# ArduinoBoardPOE.net
KiCad netlist of a schematic drawn in EAGLE
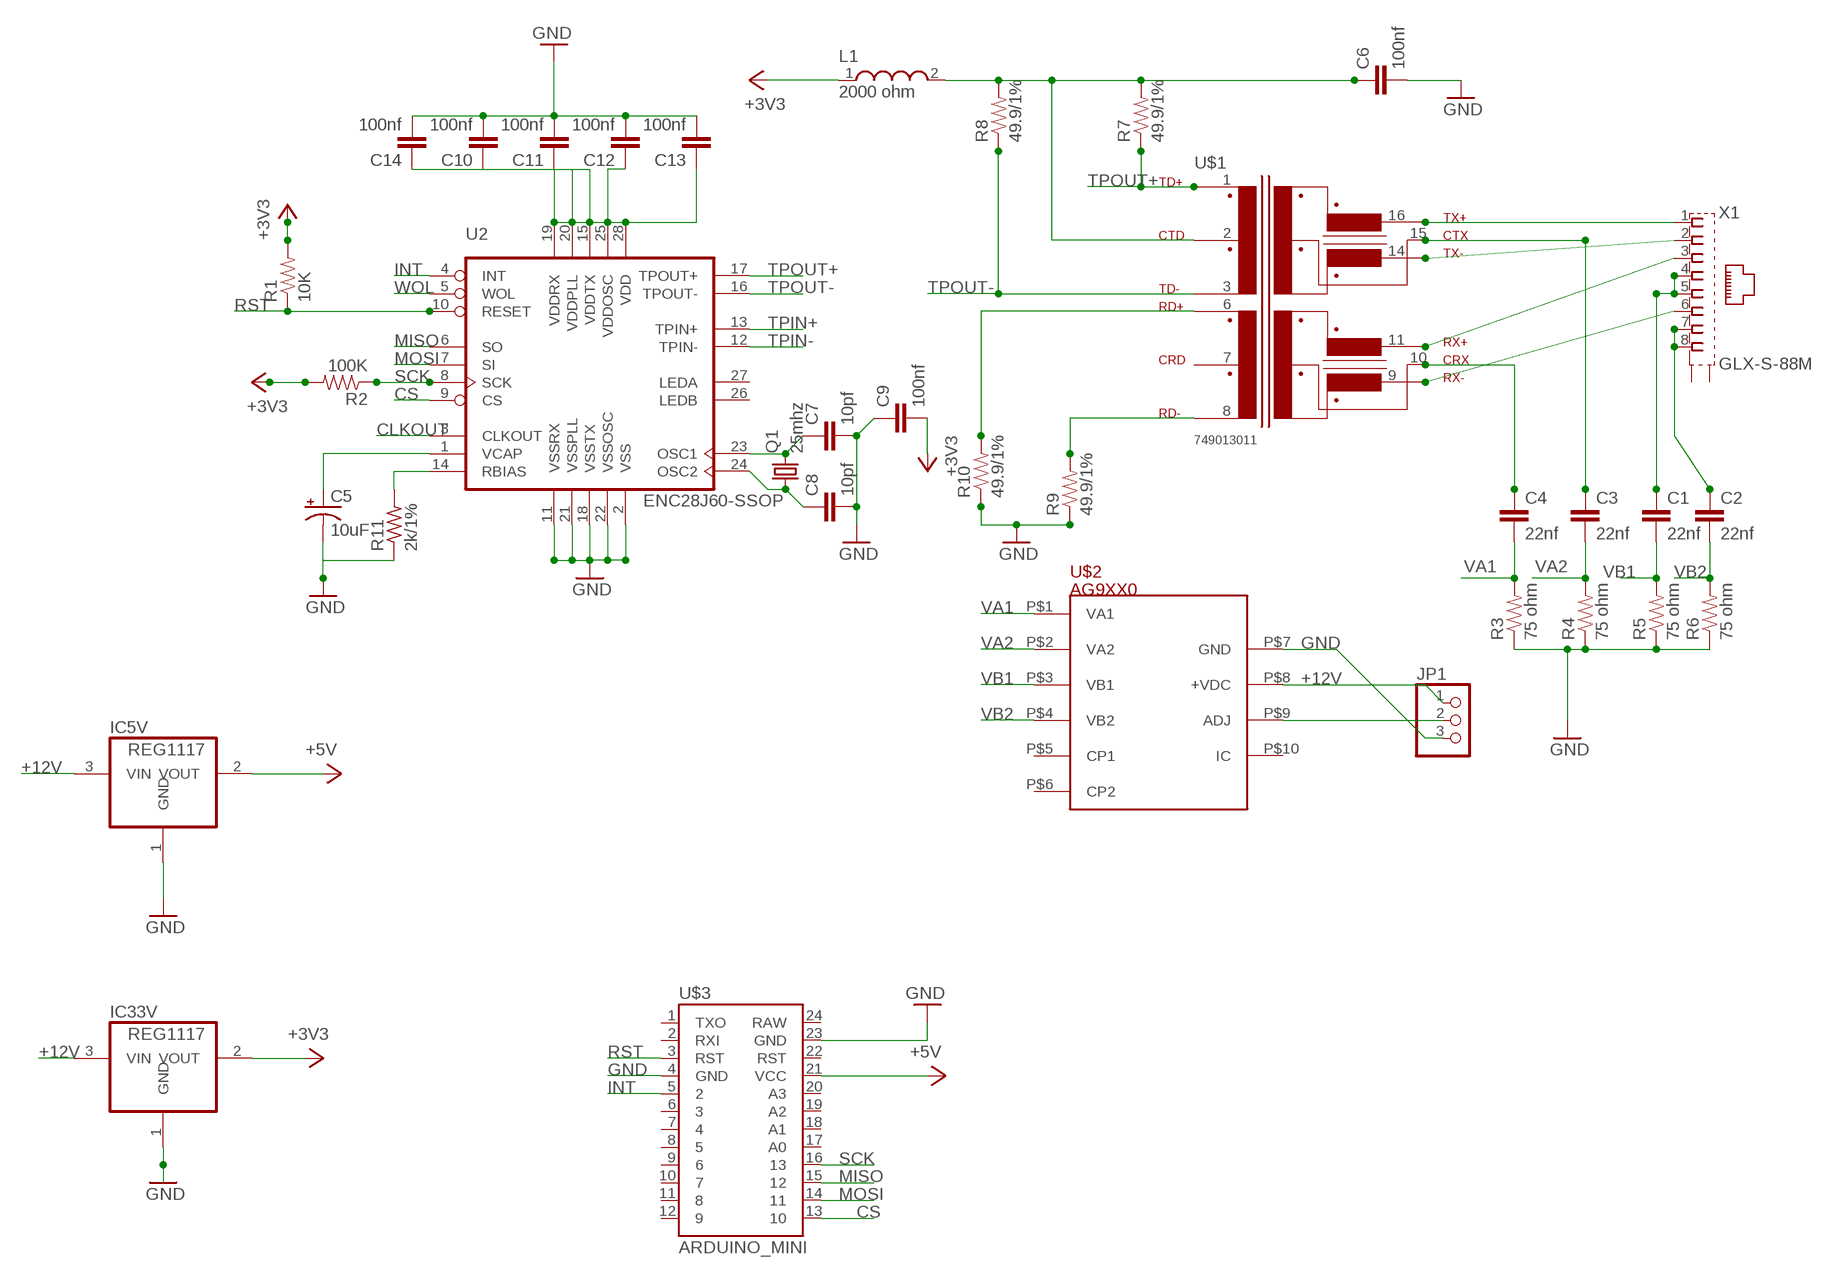
[diagram p0: schematic, sheet 1]

(export (version "E")
  (design (tool "Eeschema 10.0.6"))
  (components
    (comp (ref "C1")
      (value "22nf")
      (footprint "eagle-import:0805")
      (libsource (lib "eagle-import") (part "CAP0805"))
    )
    (comp (ref "C2")
      (value "22nf")
      (footprint "eagle-import:0805")
      (libsource (lib "eagle-import") (part "CAP0805"))
    )
    (comp (ref "C3")
      (value "22nf")
      (footprint "eagle-import:0805")
      (libsource (lib "eagle-import") (part "CAP0805"))
    )
    (comp (ref "C4")
      (value "22nf")
      (footprint "eagle-import:0805")
      (libsource (lib "eagle-import") (part "CAP0805"))
    )
    (comp (ref "C5")
      (value "10uF")
      (footprint "eagle-import:EIA3216")
      (libsource (lib "eagle-import") (part "10UF-16V-10%(TANT)"))
    )
    (comp (ref "C6")
      (value "100nf")
      (footprint "eagle-import:0805")
      (libsource (lib "eagle-import") (part "CAP0805"))
    )
    (comp (ref "C7")
      (value "10pf")
      (footprint "eagle-import:0805")
      (libsource (lib "eagle-import") (part "CAP0805"))
    )
    (comp (ref "C8")
      (value "10pf")
      (footprint "eagle-import:0805")
      (libsource (lib "eagle-import") (part "CAP0805"))
    )
    (comp (ref "C9")
      (value "100nf")
      (footprint "eagle-import:0805")
      (libsource (lib "eagle-import") (part "CAP0805"))
    )
    (comp (ref "C10")
      (value "100nf")
      (footprint "eagle-import:0805")
      (libsource (lib "eagle-import") (part "CAP0805"))
    )
    (comp (ref "C11")
      (value "100nf")
      (footprint "eagle-import:0805")
      (libsource (lib "eagle-import") (part "CAP0805"))
    )
    (comp (ref "C12")
      (value "100nf")
      (footprint "eagle-import:0805")
      (libsource (lib "eagle-import") (part "CAP0805"))
    )
    (comp (ref "C13")
      (value "100nf")
      (footprint "eagle-import:0805")
      (libsource (lib "eagle-import") (part "CAP0805"))
    )
    (comp (ref "C14")
      (value "100nf")
      (footprint "eagle-import:0805")
      (libsource (lib "eagle-import") (part "CAP0805"))
    )
    (comp (ref "IC5V")
      (value "REG1117")
      (footprint "eagle-import:SOT223")
      (libsource (lib "eagle-import") (part "REG1117"))
    )
    (comp (ref "IC33V")
      (value "REG1117")
      (footprint "eagle-import:SOT223")
      (libsource (lib "eagle-import") (part "REG1117"))
    )
    (comp (ref "JP1")
      (value "PINHD-1X3")
      (footprint "eagle-import:1X03")
      (libsource (lib "eagle-import") (part "PINHD-1X3"))
    )
    (comp (ref "L1")
      (value "2000 ohm")
      (footprint "eagle-import:WE-CBA_0805(W=3)")
      (libsource (lib "eagle-import") (part "WE-CBA_0805(WB/HS)"))
    )
    (comp (ref "Q1")
      (value "25mhz")
      (footprint "eagle-import:HC49UP")
      (libsource (lib "eagle-import") (part "CRYSTALHC49UP"))
    )
    (comp (ref "R1")
      (value "10K")
      (footprint "eagle-import:0805")
      (libsource (lib "eagle-import") (part "RESISTOR0805-RES"))
    )
    (comp (ref "R2")
      (value "100K")
      (footprint "eagle-import:0805")
      (libsource (lib "eagle-import") (part "RESISTOR0805-RES"))
    )
    (comp (ref "R3")
      (value "75 ohm")
      (footprint "eagle-import:0805")
      (libsource (lib "eagle-import") (part "RESISTOR0805-RES"))
    )
    (comp (ref "R4")
      (value "75 ohm")
      (footprint "eagle-import:0805")
      (libsource (lib "eagle-import") (part "RESISTOR0805-RES"))
    )
    (comp (ref "R5")
      (value "75 ohm")
      (footprint "eagle-import:0805")
      (libsource (lib "eagle-import") (part "RESISTOR0805-RES"))
    )
    (comp (ref "R6")
      (value "75 ohm")
      (footprint "eagle-import:0805")
      (libsource (lib "eagle-import") (part "RESISTOR0805-RES"))
    )
    (comp (ref "R7")
      (value "49.9/1%")
      (footprint "eagle-import:0805")
      (libsource (lib "eagle-import") (part "RESISTOR0805-RES"))
    )
    (comp (ref "R8")
      (value "49.9/1%")
      (footprint "eagle-import:0805")
      (libsource (lib "eagle-import") (part "RESISTOR0805-RES"))
    )
    (comp (ref "R9")
      (value "49.9/1%")
      (footprint "eagle-import:0805")
      (libsource (lib "eagle-import") (part "RESISTOR0805-RES"))
    )
    (comp (ref "R10")
      (value "49.9/1%")
      (footprint "eagle-import:0805")
      (libsource (lib "eagle-import") (part "RESISTOR0805-RES"))
    )
    (comp (ref "R11")
      (value "2k/1%")
      (footprint "eagle-import:R0805")
      (libsource (lib "eagle-import") (part "R-US_R0805"))
    )
    (comp (ref "U$1")
      (value "749013011")
      (footprint "eagle-import:749013011")
      (libsource (lib "eagle-import") (part "749013011"))
    )
    (comp (ref "U$2")
      (value "AG9XX0")
      (footprint "eagle-import:AG9000")
      (libsource (lib "eagle-import") (part "AG9XX0"))
    )
    (comp (ref "U$3")
      (value "ARDUINO_MINI")
      (footprint "eagle-import:ARDUINO_MINI")
      (libsource (lib "eagle-import") (part "ARDUINO_MINI"))
    )
    (comp (ref "U2")
      (value "ENC28J60-SSOP")
      (footprint "eagle-import:SSOP28")
      (libsource (lib "eagle-import") (part "ENC28J60-SSOP"))
    )
    (comp (ref "X1")
      (value "GLX-S-88M")
      (footprint "eagle-import:GLX-S-88M")
      (libsource (lib "eagle-import") (part "GLX-S-88M"))
    )
  )
  (nets
    (net (code "1") (name "+3V3") (class "Default")
      (node (ref "C9") (pin "2") (pinfunction "2_2") (pintype "passive"))
      (node (ref "IC33V") (pin "2") (pinfunction "VOUT_2") (pintype "output"))
      (node (ref "L1") (pin "1") (pinfunction "1_1") (pintype "passive"))
      (node (ref "R1") (pin "2") (pinfunction "2_2") (pintype "passive"))
      (node (ref "R2") (pin "2") (pinfunction "2_2") (pintype "passive"))
    )
    (net (code "2") (name "+5V") (class "Default")
      (node (ref "IC5V") (pin "2") (pinfunction "VOUT_2") (pintype "output"))
      (node (ref "U$3") (pin "21") (pinfunction "VCC_21") (pintype "bidirectional"))
    )
    (net (code "3") (name "/+12V") (class "Default")
      (node (ref "IC33V") (pin "3") (pinfunction "VIN_3") (pintype "input"))
      (node (ref "IC5V") (pin "3") (pinfunction "VIN_3") (pintype "input"))
      (node (ref "JP1") (pin "1") (pinfunction "1_1") (pintype "passive"))
      (node (ref "U$2") (pin "P$8") (pinfunction "+VDC_P$8") (pintype "power_in"))
    )
    (net (code "4") (name "/CLKOUT") (class "Default")
      (node (ref "U2") (pin "3") (pinfunction "CLKOUT_3") (pintype "output"))
    )
    (net (code "5") (name "/CS") (class "Default")
      (node (ref "U$3") (pin "13") (pinfunction "10_13") (pintype "bidirectional"))
      (node (ref "U2") (pin "9") (pinfunction "CS_9") (pintype "input"))
    )
    (net (code "6") (name "/INT") (class "Default")
      (node (ref "U$3") (pin "5") (pinfunction "2_5") (pintype "bidirectional"))
      (node (ref "U2") (pin "4") (pinfunction "INT_4") (pintype "output"))
    )
    (net (code "7") (name "/MISO") (class "Default")
      (node (ref "U$3") (pin "15") (pinfunction "12_15") (pintype "bidirectional"))
      (node (ref "U2") (pin "6") (pinfunction "SO_6") (pintype "output"))
    )
    (net (code "8") (name "/MOSI") (class "Default")
      (node (ref "U$3") (pin "14") (pinfunction "11_14") (pintype "bidirectional"))
      (node (ref "U2") (pin "7") (pinfunction "SI_7") (pintype "input"))
    )
    (net (code "9") (name "/RST") (class "Default")
      (node (ref "R1") (pin "1") (pinfunction "1_1") (pintype "passive"))
      (node (ref "U$3") (pin "3") (pinfunction "RST_3") (pintype "bidirectional"))
      (node (ref "U2") (pin "10") (pinfunction "RESET_10") (pintype "input"))
    )
    (net (code "10") (name "/SCK") (class "Default")
      (node (ref "R2") (pin "1") (pinfunction "1_1") (pintype "passive"))
      (node (ref "U$3") (pin "16") (pinfunction "13_16") (pintype "bidirectional"))
      (node (ref "U2") (pin "8") (pinfunction "SCK_8") (pintype "input"))
    )
    (net (code "11") (name "/TPIN+") (class "Default")
      (node (ref "R10") (pin "2") (pinfunction "2_2") (pintype "passive"))
      (node (ref "U$1") (pin "6") (pinfunction "4_6") (pintype "passive"))
      (node (ref "U2") (pin "13") (pinfunction "TPIN+_13") (pintype "input"))
    )
    (net (code "12") (name "/TPIN-") (class "Default")
      (node (ref "R9") (pin "2") (pinfunction "2_2") (pintype "passive"))
      (node (ref "U$1") (pin "8") (pinfunction "6_8") (pintype "passive"))
      (node (ref "U2") (pin "12") (pinfunction "TPIN-_12") (pintype "input"))
    )
    (net (code "13") (name "/TPOUT+") (class "Default")
      (node (ref "R7") (pin "1") (pinfunction "1_1") (pintype "passive"))
      (node (ref "U$1") (pin "1") (pinfunction "1_1") (pintype "passive"))
      (node (ref "U2") (pin "17") (pinfunction "TPOUT+_17") (pintype "output"))
    )
    (net (code "14") (name "/TPOUT-") (class "Default")
      (node (ref "R8") (pin "1") (pinfunction "1_1") (pintype "passive"))
      (node (ref "U$1") (pin "3") (pinfunction "3_3") (pintype "passive"))
      (node (ref "U2") (pin "16") (pinfunction "TPOUT-_16") (pintype "output"))
    )
    (net (code "15") (name "/VA1") (class "Default")
      (node (ref "C4") (pin "2") (pinfunction "2_2") (pintype "passive"))
      (node (ref "R3") (pin "2") (pinfunction "2_2") (pintype "passive"))
      (node (ref "U$2") (pin "P$1") (pinfunction "VA1_P$1") (pintype "input"))
    )
    (net (code "16") (name "/VA2") (class "Default")
      (node (ref "C3") (pin "2") (pinfunction "2_2") (pintype "passive"))
      (node (ref "R4") (pin "2") (pinfunction "2_2") (pintype "passive"))
      (node (ref "U$2") (pin "P$2") (pinfunction "VA2_P$2") (pintype "input"))
    )
    (net (code "17") (name "/VB1") (class "Default")
      (node (ref "C1") (pin "2") (pinfunction "2_2") (pintype "passive"))
      (node (ref "R5") (pin "2") (pinfunction "2_2") (pintype "passive"))
      (node (ref "U$2") (pin "P$3") (pinfunction "VB1_P$3") (pintype "input"))
    )
    (net (code "18") (name "/VB2") (class "Default")
      (node (ref "C2") (pin "2") (pinfunction "2_2") (pintype "passive"))
      (node (ref "R6") (pin "2") (pinfunction "2_2") (pintype "passive"))
      (node (ref "U$2") (pin "P$4") (pinfunction "VB2_P$4") (pintype "input"))
    )
    (net (code "19") (name "/WOL") (class "Default")
      (node (ref "U2") (pin "5") (pinfunction "WOL_5") (pintype "output"))
    )
    (net (code "20") (name "GND") (class "Default")
      (node (ref "C10") (pin "2") (pinfunction "2_2") (pintype "passive"))
      (node (ref "C11") (pin "2") (pinfunction "2_2") (pintype "passive"))
      (node (ref "C12") (pin "2") (pinfunction "2_2") (pintype "passive"))
      (node (ref "C13") (pin "2") (pinfunction "2_2") (pintype "passive"))
      (node (ref "C14") (pin "2") (pinfunction "2_2") (pintype "passive"))
      (node (ref "C5") (pin "C") (pinfunction "-_C") (pintype "passive"))
      (node (ref "C6") (pin "2") (pinfunction "2_2") (pintype "passive"))
      (node (ref "C7") (pin "2") (pinfunction "2_2") (pintype "passive"))
      (node (ref "C8") (pin "2") (pinfunction "2_2") (pintype "passive"))
      (node (ref "C9") (pin "1") (pinfunction "1_1") (pintype "passive"))
      (node (ref "IC33V") (pin "1") (pinfunction "GND_1") (pintype "power_in"))
      (node (ref "IC5V") (pin "1") (pinfunction "GND_1") (pintype "power_in"))
      (node (ref "JP1") (pin "3") (pinfunction "3_3") (pintype "passive"))
      (node (ref "R10") (pin "1") (pinfunction "1_1") (pintype "passive"))
      (node (ref "R11") (pin "1") (pinfunction "1_1") (pintype "passive"))
      (node (ref "R3") (pin "1") (pinfunction "1_1") (pintype "passive"))
      (node (ref "R4") (pin "1") (pinfunction "1_1") (pintype "passive"))
      (node (ref "R5") (pin "1") (pinfunction "1_1") (pintype "passive"))
      (node (ref "R6") (pin "1") (pinfunction "1_1") (pintype "passive"))
      (node (ref "R9") (pin "1") (pinfunction "1_1") (pintype "passive"))
      (node (ref "U$2") (pin "P$7") (pinfunction "GND_P$7") (pintype "power_in"))
      (node (ref "U$3") (pin "23") (pinfunction "GND_23") (pintype "bidirectional"))
      (node (ref "U$3") (pin "4") (pinfunction "GND_4") (pintype "bidirectional"))
      (node (ref "U2") (pin "11") (pinfunction "VSSRX_11") (pintype "power_in"))
      (node (ref "U2") (pin "18") (pinfunction "VSSTX_18") (pintype "power_in"))
      (node (ref "U2") (pin "2") (pinfunction "VSS_2") (pintype "power_in"))
      (node (ref "U2") (pin "21") (pinfunction "VSSPLL_21") (pintype "power_in"))
      (node (ref "U2") (pin "22") (pinfunction "VSSOSC_22") (pintype "power_in"))
    )
    (net (code "21") (name "Net-(C1-Pad1)") (class "Default")
      (node (ref "C1") (pin "1") (pinfunction "1_1") (pintype "passive"))
      (node (ref "X1") (pin "4") (pinfunction "4_4") (pintype "passive"))
      (node (ref "X1") (pin "5") (pinfunction "5_5") (pintype "passive"))
    )
    (net (code "22") (name "Net-(C2-Pad1)") (class "Default")
      (node (ref "C2") (pin "1") (pinfunction "1_1") (pintype "passive"))
      (node (ref "X1") (pin "7") (pinfunction "7_7") (pintype "passive"))
      (node (ref "X1") (pin "8") (pinfunction "8_8") (pintype "passive"))
    )
    (net (code "23") (name "Net-(C5-+)") (class "Default")
      (node (ref "C5") (pin "A") (pinfunction "+_A") (pintype "passive"))
      (node (ref "U2") (pin "1") (pinfunction "VCAP_1") (pintype "power_in"))
    )
    (net (code "24") (name "Net-(C6-Pad1)") (class "Default")
      (node (ref "C6") (pin "1") (pinfunction "1_1") (pintype "passive"))
      (node (ref "L1") (pin "2") (pinfunction "2_2") (pintype "passive"))
      (node (ref "R7") (pin "2") (pinfunction "2_2") (pintype "passive"))
      (node (ref "R8") (pin "2") (pinfunction "2_2") (pintype "passive"))
      (node (ref "U$1") (pin "2") (pinfunction "2_2") (pintype "passive"))
    )
    (net (code "25") (name "Net-(U$1-7)") (class "Default")
      (node (ref "U$1") (pin "16") (pinfunction "7_16") (pintype "passive"))
      (node (ref "X1") (pin "1") (pinfunction "1_1") (pintype "passive"))
    )
    (net (code "26") (name "Net-(U$1-8)") (class "Default")
      (node (ref "C3") (pin "1") (pinfunction "1_1") (pintype "passive"))
      (node (ref "U$1") (pin "15") (pinfunction "8_15") (pintype "passive"))
    )
    (net (code "27") (name "Net-(U$1-9)") (class "Default")
      (node (ref "U$1") (pin "14") (pinfunction "9_14") (pintype "passive"))
      (node (ref "X1") (pin "2") (pinfunction "2_2") (pintype "passive"))
    )
    (net (code "28") (name "Net-(U$1-10)") (class "Default")
      (node (ref "U$1") (pin "11") (pinfunction "10_11") (pintype "passive"))
      (node (ref "X1") (pin "3") (pinfunction "3_3") (pintype "passive"))
    )
    (net (code "29") (name "Net-(U$1-11)") (class "Default")
      (node (ref "C4") (pin "1") (pinfunction "1_1") (pintype "passive"))
      (node (ref "U$1") (pin "10") (pinfunction "11_10") (pintype "passive"))
    )
    (net (code "30") (name "Net-(U$1-12)") (class "Default")
      (node (ref "U$1") (pin "9") (pinfunction "12_9") (pintype "passive"))
      (node (ref "X1") (pin "6") (pinfunction "6_6") (pintype "passive"))
    )
    (net (code "31") (name "Net-(U$2-ADJ)") (class "Default")
      (node (ref "JP1") (pin "2") (pinfunction "2_2") (pintype "passive"))
      (node (ref "U$2") (pin "P$9") (pinfunction "ADJ_P$9") (pintype "passive"))
    )
    (net (code "32") (name "Net-(U2-OSC1)") (class "Default")
      (node (ref "C7") (pin "1") (pinfunction "1_1") (pintype "passive"))
      (node (ref "Q1") (pin "2") (pinfunction "2_2") (pintype "passive"))
      (node (ref "U2") (pin "23") (pinfunction "OSC1_23") (pintype "input"))
    )
    (net (code "33") (name "Net-(U2-OSC2)") (class "Default")
      (node (ref "C8") (pin "1") (pinfunction "1_1") (pintype "passive"))
      (node (ref "Q1") (pin "1") (pinfunction "1_1") (pintype "passive"))
      (node (ref "U2") (pin "24") (pinfunction "OSC2_24") (pintype "output"))
    )
    (net (code "34") (name "Net-(U2-RBIAS)") (class "Default")
      (node (ref "R11") (pin "2") (pinfunction "2_2") (pintype "passive"))
      (node (ref "U2") (pin "14") (pinfunction "RBIAS_14") (pintype "passive"))
    )
    (net (code "35") (name "Net-(U2-VDD)") (class "Default")
      (node (ref "C10") (pin "1") (pinfunction "1_1") (pintype "passive"))
      (node (ref "C11") (pin "1") (pinfunction "1_1") (pintype "passive"))
      (node (ref "C12") (pin "1") (pinfunction "1_1") (pintype "passive"))
      (node (ref "C13") (pin "1") (pinfunction "1_1") (pintype "passive"))
      (node (ref "C14") (pin "1") (pinfunction "1_1") (pintype "passive"))
      (node (ref "U2") (pin "15") (pinfunction "VDDTX_15") (pintype "power_in"))
      (node (ref "U2") (pin "19") (pinfunction "VDDRX_19") (pintype "power_in"))
      (node (ref "U2") (pin "20") (pinfunction "VDDPLL_20") (pintype "power_in"))
      (node (ref "U2") (pin "25") (pinfunction "VDDOSC_25") (pintype "power_in"))
      (node (ref "U2") (pin "28") (pinfunction "VDD_28") (pintype "power_in"))
    )
    (net (code "36") (name "unconnected-(U$1-5-Pad7)") (class "Default")
      (node (ref "U$1") (pin "7") (pinfunction "5_7") (pintype "passive"))
    )
    (net (code "37") (name "unconnected-(U$2-CP1-PadP$5)") (class "Default")
      (node (ref "U$2") (pin "P$5") (pinfunction "CP1_P$5") (pintype "input"))
    )
    (net (code "38") (name "unconnected-(U$2-CP2-PadP$6)") (class "Default")
      (node (ref "U$2") (pin "P$6") (pinfunction "CP2_P$6") (pintype "input"))
    )
    (net (code "39") (name "unconnected-(U$2-IC-PadP$10)") (class "Default")
      (node (ref "U$2") (pin "P$10") (pinfunction "IC_P$10") (pintype "no_connect"))
    )
    (net (code "40") (name "unconnected-(U$3-3-Pad6)") (class "Default")
      (node (ref "U$3") (pin "6") (pinfunction "3_6") (pintype "bidirectional"))
    )
    (net (code "41") (name "unconnected-(U$3-4-Pad7)") (class "Default")
      (node (ref "U$3") (pin "7") (pinfunction "4_7") (pintype "bidirectional"))
    )
    (net (code "42") (name "unconnected-(U$3-5-Pad8)") (class "Default")
      (node (ref "U$3") (pin "8") (pinfunction "5_8") (pintype "bidirectional"))
    )
    (net (code "43") (name "unconnected-(U$3-6-Pad9)") (class "Default")
      (node (ref "U$3") (pin "9") (pinfunction "6_9") (pintype "bidirectional"))
    )
    (net (code "44") (name "unconnected-(U$3-7-Pad10)") (class "Default")
      (node (ref "U$3") (pin "10") (pinfunction "7_10") (pintype "bidirectional"))
    )
    (net (code "45") (name "unconnected-(U$3-8-Pad11)") (class "Default")
      (node (ref "U$3") (pin "11") (pinfunction "8_11") (pintype "bidirectional"))
    )
    (net (code "46") (name "unconnected-(U$3-9-Pad12)") (class "Default")
      (node (ref "U$3") (pin "12") (pinfunction "9_12") (pintype "bidirectional"))
    )
    (net (code "47") (name "unconnected-(U$3-A0-Pad17)") (class "Default")
      (node (ref "U$3") (pin "17") (pinfunction "A0_17") (pintype "bidirectional"))
    )
    (net (code "48") (name "unconnected-(U$3-A1-Pad18)") (class "Default")
      (node (ref "U$3") (pin "18") (pinfunction "A1_18") (pintype "bidirectional"))
    )
    (net (code "49") (name "unconnected-(U$3-A2-Pad19)") (class "Default")
      (node (ref "U$3") (pin "19") (pinfunction "A2_19") (pintype "bidirectional"))
    )
    (net (code "50") (name "unconnected-(U$3-A3-Pad20)") (class "Default")
      (node (ref "U$3") (pin "20") (pinfunction "A3_20") (pintype "bidirectional"))
    )
    (net (code "51") (name "unconnected-(U$3-RAW-Pad24)") (class "Default")
      (node (ref "U$3") (pin "24") (pinfunction "RAW_24") (pintype "bidirectional"))
    )
    (net (code "52") (name "unconnected-(U$3-RST-Pad22)") (class "Default")
      (node (ref "U$3") (pin "22") (pinfunction "RST_22") (pintype "bidirectional"))
    )
    (net (code "53") (name "unconnected-(U$3-RXI-Pad2)") (class "Default")
      (node (ref "U$3") (pin "2") (pinfunction "RXI_2") (pintype "bidirectional"))
    )
    (net (code "54") (name "unconnected-(U$3-TXO-Pad1)") (class "Default")
      (node (ref "U$3") (pin "1") (pinfunction "TXO_1") (pintype "bidirectional"))
    )
    (net (code "55") (name "unconnected-(U2-LEDA-Pad27)") (class "Default")
      (node (ref "U2") (pin "27") (pinfunction "LEDA_27") (pintype "output"))
    )
    (net (code "56") (name "unconnected-(U2-LEDB-Pad26)") (class "Default")
      (node (ref "U2") (pin "26") (pinfunction "LEDB_26") (pintype "output"))
    )
    (net (code "57") (name "unconnected-(X1-PadS1)") (class "Default")
      (node (ref "X1") (pin "S1") (pinfunction "S1_S1") (pintype "passive"))
    )
    (net (code "58") (name "unconnected-(X1-PadS2)") (class "Default")
      (node (ref "X1") (pin "S2") (pinfunction "S2_S2") (pintype "passive"))
    )
  )
)
